# LED.net
KiCad netlist of a schematic drawn in Altium Designer
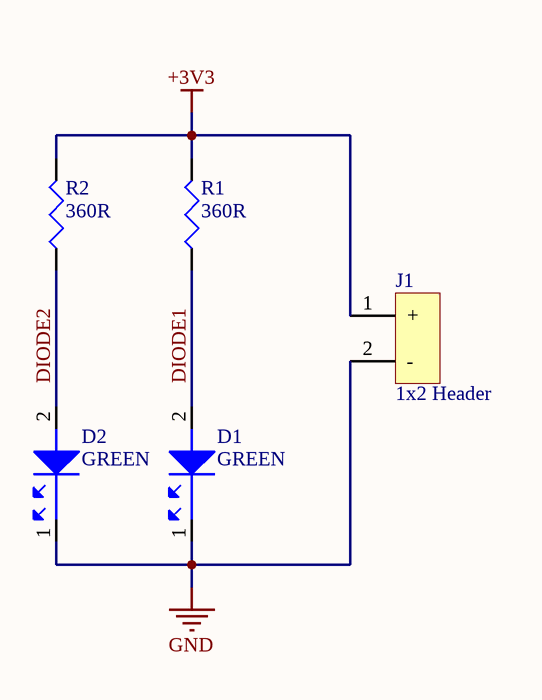
[diagram p0: LED.SchDoc]

(export (version "E")
  (design (tool "Eeschema 10.0.6"))
  (components
    (comp (ref "D1")
      (value "GREEN")
      (footprint "LED0603G")
      (description "LED GREEN ESS II SMD")
      (fields
        (field (name "MANUFACTURER") "Panasonic SSG")
        (field (name "MANUFACTURER PART NUMBER") "LNJ337W83RA")
      )
      (libsource (lib "LED_Schlib") (part "LNJ337W83RA"))
    )
    (comp (ref "D2")
      (value "GREEN")
      (footprint "LED0603G")
      (description "LED GREEN ESS II SMD")
      (fields
        (field (name "MANUFACTURER") "Panasonic SSG")
        (field (name "MANUFACTURER PART NUMBER") "LNJ337W83RA")
      )
      (libsource (lib "LED_Schlib") (part "LNJ337W83RA"))
    )
    (comp (ref "J1")
      (value "1x2 Header")
      (footprint "HDR1X2")
      (description "Conn Wire to Board HDR 2 POS 2.54mm Solder ST Thru-Hole Bag")
      (fields (field (name "MANUFACTURER") "Molex") (field (name "MANUFACTURER PART NUMBER") "22-29-2021"))
      (libsource (lib "LED_Schlib") (part "22-29-2021"))
    )
    (comp (ref "R1")
      (value "360R")
      (footprint "R0805")
      (description "Res Thick Film 0805 360 Ohm 1% 0.125W(1/8W) ±100ppm/C Molded SMD Automotive Paper T/R")
      (fields
        (field (name "MANUFACTURER") "Vishay")
        (field (name "MANUFACTURER PART NUMBER") "CRCW0805360RFKEA")
      )
      (libsource (lib "LED_Schlib") (part "CRCW0805360RFKEA"))
    )
    (comp (ref "R2")
      (value "360R")
      (footprint "R0805")
      (description "Res Thick Film 0805 360 Ohm 1% 0.125W(1/8W) ±100ppm/C Molded SMD Automotive Paper T/R")
      (fields
        (field (name "MANUFACTURER") "Vishay")
        (field (name "MANUFACTURER PART NUMBER") "CRCW0805360RFKEA")
      )
      (libsource (lib "LED_Schlib") (part "CRCW0805360RFKEA"))
    )
  )
  (nets
    (net (code "1") (name "+3V3") (class "Default")
      (node (ref "J1") (pin "1") (pinfunction "+_1") (pintype "passive"))
      (node (ref "R1") (pin "2") (pinfunction "2_2") (pintype "passive"))
      (node (ref "R2") (pin "2") (pinfunction "2_2") (pintype "passive"))
    )
    (net (code "2") (name "/DIODE1") (class "Default")
      (node (ref "D1") (pin "2") (pinfunction "2_2") (pintype "passive"))
      (node (ref "R1") (pin "1") (pinfunction "1_1") (pintype "passive"))
    )
    (net (code "3") (name "/DIODE2") (class "Default")
      (node (ref "D2") (pin "2") (pinfunction "2_2") (pintype "passive"))
      (node (ref "R2") (pin "1") (pinfunction "1_1") (pintype "passive"))
    )
    (net (code "4") (name "GND") (class "Default")
      (node (ref "D1") (pin "1") (pinfunction "1_1") (pintype "passive"))
      (node (ref "D2") (pin "1") (pinfunction "1_1") (pintype "passive"))
      (node (ref "J1") (pin "2") (pinfunction "-_2") (pintype "passive"))
    )
  )
)
